# power_supplies.net
KiCad netlist of a schematic drawn in Altium Designer
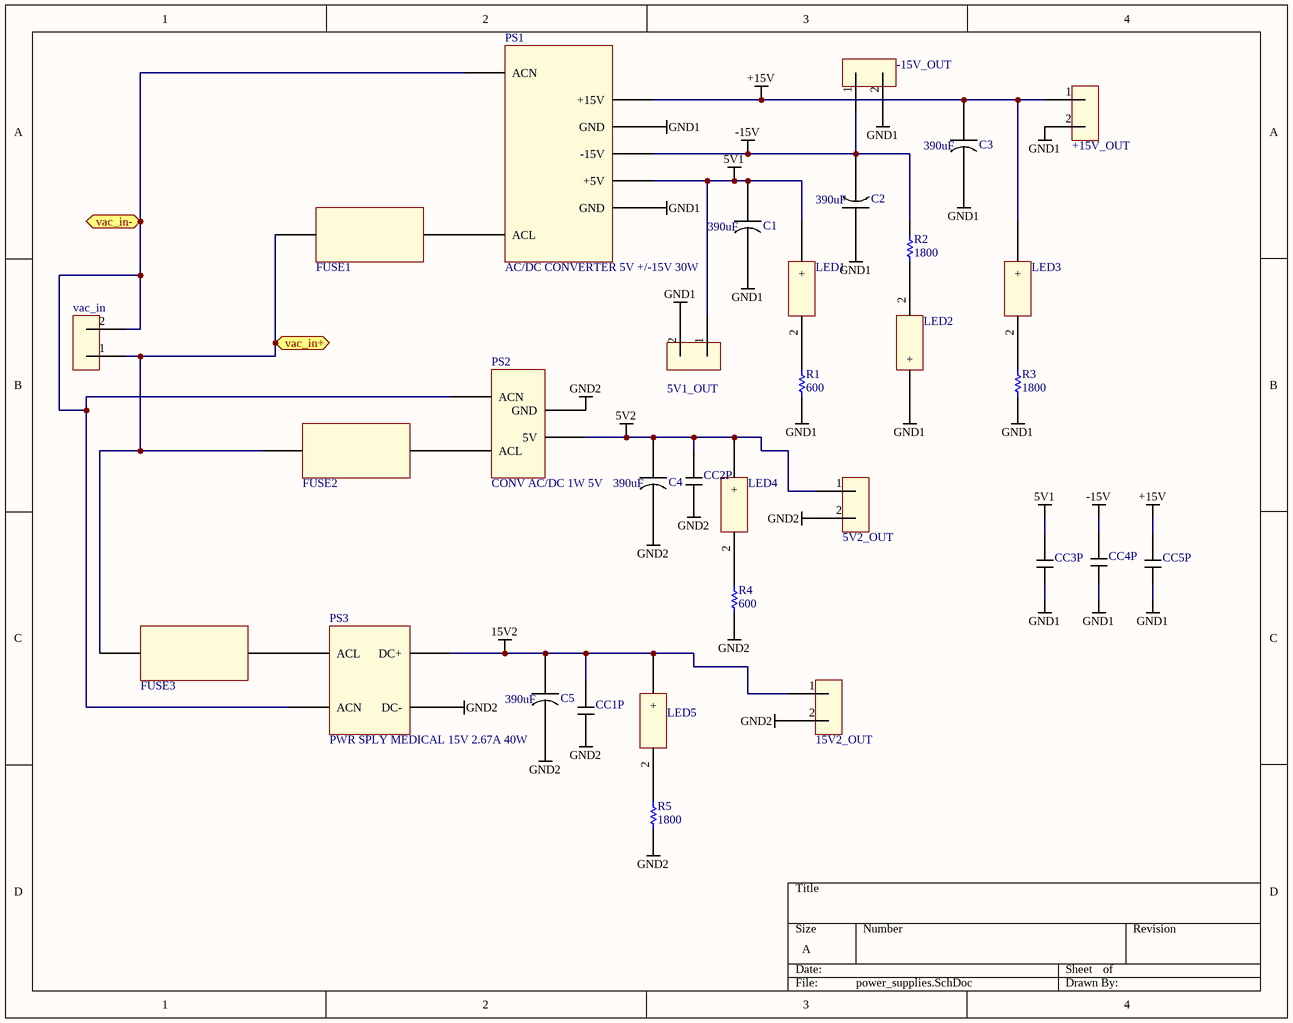
[diagram p0: power_supplies.SchDoc]

(export (version "E")
  (design (tool "Eeschema 10.0.6"))
  (components
    (comp (ref "+15V_OUT")
      (value "5MM_HOR_ENTRY")
      (footprint "5MM_HOR_ENTRY")
      (libsource (lib "") (part "5MM_HOR_ENTRY_1"))
    )
    (comp (ref "-15V_OUT")
      (value "5MM_HOR_ENTRY")
      (footprint "5MM_HOR_ENTRY")
      (libsource (lib "") (part "5MM_HOR_ENTRY_3"))
    )
    (comp (ref "5V1_OUT")
      (value "5MM_HOR_ENTRY")
      (footprint "5MM_HOR_ENTRY")
      (libsource (lib "smartChargerLibrary") (part "5MM_HOR_ENTRY"))
    )
    (comp (ref "5V2_OUT")
      (value "5MM_HOR_ENTRY")
      (footprint "5MM_HOR_ENTRY")
      (libsource (lib "") (part "5MM_HOR_ENTRY_1"))
    )
    (comp (ref "15V2_OUT")
      (value "5MM_HOR_ENTRY")
      (footprint "5MM_HOR_ENTRY")
      (libsource (lib "") (part "5MM_HOR_ENTRY_1"))
    )
    (comp (ref "C1")
      (value "C1")
      (footprint "Cap_Pol_5mm")
      (fields (field (name "CAPACITANCE") "390uF"))
      (libsource (lib "smartChargerLibrary") (part "Cap_Pol_5"))
    )
    (comp (ref "C2")
      (value "C1")
      (footprint "Cap_Pol_5mm")
      (fields (field (name "CAPACITANCE") "390uF"))
      (libsource (lib "smartChargerLibrary") (part "Cap_Pol_5"))
    )
    (comp (ref "C3")
      (value "C1")
      (footprint "Cap_Pol_5mm")
      (fields (field (name "CAPACITANCE") "390uF"))
      (libsource (lib "smartChargerLibrary") (part "Cap_Pol_5"))
    )
    (comp (ref "C4")
      (value "C1")
      (footprint "Cap_Pol_5mm")
      (fields (field (name "CAPACITANCE") "390uF"))
      (libsource (lib "smartChargerLibrary") (part "Cap_Pol_5"))
    )
    (comp (ref "C5")
      (value "C1")
      (footprint "Cap_Pol_5mm")
      (fields (field (name "CAPACITANCE") "390uF"))
      (libsource (lib "smartChargerLibrary") (part "Cap_Pol_5"))
    )
    (comp (ref "CC1P")
      (value "CAP_CERAM_5MM")
      (footprint "CAP_CERAM_5MM")
      (libsource (lib "smartChargerLibrary") (part "CAP_CERAM_5MM"))
    )
    (comp (ref "CC2P")
      (value "CAP_CERAM_5MM")
      (footprint "CAP_CERAM_5MM")
      (libsource (lib "smartChargerLibrary") (part "CAP_CERAM_5MM"))
    )
    (comp (ref "CC3P")
      (value "CAP_CERAM_5MM")
      (footprint "CAP_CERAM_5MM")
      (libsource (lib "smartChargerLibrary") (part "CAP_CERAM_5MM"))
    )
    (comp (ref "CC4P")
      (value "CAP_CERAM_5MM")
      (footprint "CAP_CERAM_5MM")
      (libsource (lib "smartChargerLibrary") (part "CAP_CERAM_5MM"))
    )
    (comp (ref "CC5P")
      (value "CAP_CERAM_5MM")
      (footprint "CAP_CERAM_5MM")
      (libsource (lib "smartChargerLibrary") (part "CAP_CERAM_5MM"))
    )
    (comp (ref "FUSE1")
      (value "fuse < 5A")
      (footprint "Fuse < 5A")
      (libsource (lib "smartChargerLibrary") (part "fuse {lt} 5A"))
    )
    (comp (ref "FUSE2")
      (value "fuse < 5A")
      (footprint "Fuse < 5A")
      (libsource (lib "smartChargerLibrary") (part "fuse {lt} 5A"))
    )
    (comp (ref "FUSE3")
      (value "fuse < 5A")
      (footprint "Fuse < 5A")
      (libsource (lib "smartChargerLibrary") (part "fuse {lt} 5A"))
    )
    (comp (ref "LED1") (value "LED") (footprint "LED") (libsource (lib "smartChargerLibrary") (part "LED")))
    (comp (ref "LED2") (value "LED") (footprint "LED") (libsource (lib "") (part "LED_1")))
    (comp (ref "LED3") (value "LED") (footprint "LED") (libsource (lib "smartChargerLibrary") (part "LED")))
    (comp (ref "LED4") (value "LED") (footprint "LED") (libsource (lib "smartChargerLibrary") (part "LED")))
    (comp (ref "LED5") (value "LED") (footprint "LED") (libsource (lib "smartChargerLibrary") (part "LED")))
    (comp (ref "PS1")
      (value "AC/DC CONVERTER 5V +/-15V 30W")
      (footprint "AC/DC CONVERTER 5V +/-15V 30W")
      (libsource (lib "smartChargerLibrary") (part "AC/DC CONVERTER 5V +/-15V 30W"))
    )
    (comp (ref "PS2")
      (value "CONV AC/DC 1W 5V")
      (footprint "CONV AC/DC 1W 5V")
      (libsource (lib "smartChargerLibrary") (part "CONV AC/DC 1W 5V"))
    )
    (comp (ref "PS3")
      (value "PWR SPLY MEDICAL 15V 2.67A 40W")
      (footprint "PWR SPLY MEDICAL 15V 2.67A 40W")
      (libsource (lib "smartChargerLibrary") (part "PWR SPLY MEDICAL 15V 2.67A 40W"))
    )
    (comp (ref "R1")
      (value "600")
      (footprint "AXIAL-0.3")
      (description "Resistor")
      (fields (field (name "Comment") "Res1") (field (name "PUBLISHER") "Altium Limited"))
      (libsource (lib "Miscellaneous Devices") (part "Res1"))
    )
    (comp (ref "R2")
      (value "1800")
      (footprint "AXIAL-0.3")
      (description "Resistor")
      (fields (field (name "Comment") "Res1") (field (name "PUBLISHER") "Altium Limited"))
      (libsource (lib "Miscellaneous Devices") (part "Res1"))
    )
    (comp (ref "R3")
      (value "1800")
      (footprint "AXIAL-0.3")
      (description "Resistor")
      (fields (field (name "Comment") "Res1") (field (name "PUBLISHER") "Altium Limited"))
      (libsource (lib "Miscellaneous Devices") (part "Res1"))
    )
    (comp (ref "R4")
      (value "600")
      (footprint "AXIAL-0.3")
      (description "Resistor")
      (fields (field (name "Comment") "Res1") (field (name "PUBLISHER") "Altium Limited"))
      (libsource (lib "Miscellaneous Devices") (part "Res1"))
    )
    (comp (ref "R5")
      (value "1800")
      (footprint "AXIAL-0.3")
      (description "Resistor")
      (fields (field (name "Comment") "Res1") (field (name "PUBLISHER") "Altium Limited"))
      (libsource (lib "Miscellaneous Devices") (part "Res1"))
    )
    (comp (ref "vac_in")
      (value "5MM_HOR_ENTRY")
      (footprint "5MM_HOR_ENTRY")
      (libsource (lib "") (part "5MM_HOR_ENTRY_2"))
    )
  )
  (nets
    (net (code "1") (name "+15V") (class "Default")
      (node (ref "+15V_OUT") (pin "1") (pinfunction "1_1") (pintype "passive"))
      (node (ref "C3") (pin "1") (pinfunction "1_1") (pintype "passive"))
      (node (ref "CC5P") (pin "1") (pinfunction "1_1") (pintype "passive"))
      (node (ref "LED3") (pin "1") (pinfunction "+_1") (pintype "passive"))
      (node (ref "PS1") (pin "5") (pinfunction "+15V_5") (pintype "passive"))
    )
    (net (code "2") (name "-15V") (class "Default")
      (node (ref "-15V_OUT") (pin "1") (pinfunction "1_1") (pintype "passive"))
      (node (ref "C2") (pin "2") (pinfunction "2_2") (pintype "passive"))
      (node (ref "CC4P") (pin "1") (pinfunction "1_1") (pintype "passive"))
      (node (ref "PS1") (pin "3") (pinfunction "-15V_3") (pintype "passive"))
      (node (ref "R2") (pin "1") (pinfunction "1_1") (pintype "passive"))
    )
    (net (code "3") (name "/vac_in+") (class "Default")
      (node (ref "FUSE1") (pin "1") (pinfunction "1_1") (pintype "passive"))
      (node (ref "FUSE2") (pin "1") (pinfunction "1_1") (pintype "passive"))
      (node (ref "FUSE3") (pin "1") (pinfunction "1_1") (pintype "passive"))
      (node (ref "vac_in") (pin "1") (pinfunction "1_1") (pintype "passive"))
    )
    (net (code "4") (name "/vac_in-") (class "Default")
      (node (ref "PS1") (pin "ACN") (pinfunction "ACN_ACN") (pintype "passive"))
      (node (ref "PS2") (pin "1") (pinfunction "ACN_1") (pintype "passive"))
      (node (ref "PS3") (pin "2") (pinfunction "ACN_2") (pintype "passive"))
      (node (ref "vac_in") (pin "2") (pinfunction "2_2") (pintype "passive"))
    )
    (net (code "5") (name "5V1") (class "Default")
      (node (ref "5V1_OUT") (pin "1") (pinfunction "1_1") (pintype "passive"))
      (node (ref "C1") (pin "1") (pinfunction "1_1") (pintype "passive"))
      (node (ref "CC3P") (pin "1") (pinfunction "1_1") (pintype "passive"))
      (node (ref "LED1") (pin "1") (pinfunction "+_1") (pintype "passive"))
      (node (ref "PS1") (pin "2") (pinfunction "+5V_2") (pintype "passive"))
    )
    (net (code "6") (name "5V2") (class "Default")
      (node (ref "5V2_OUT") (pin "1") (pinfunction "1_1") (pintype "passive"))
      (node (ref "C4") (pin "1") (pinfunction "1_1") (pintype "passive"))
      (node (ref "CC2P") (pin "1") (pinfunction "1_1") (pintype "passive"))
      (node (ref "LED4") (pin "1") (pinfunction "+_1") (pintype "passive"))
      (node (ref "PS2") (pin "4") (pinfunction "5V_4") (pintype "passive"))
    )
    (net (code "7") (name "15V2") (class "Default")
      (node (ref "15V2_OUT") (pin "1") (pinfunction "1_1") (pintype "passive"))
      (node (ref "C5") (pin "1") (pinfunction "1_1") (pintype "passive"))
      (node (ref "CC1P") (pin "1") (pinfunction "1_1") (pintype "passive"))
      (node (ref "LED5") (pin "1") (pinfunction "+_1") (pintype "passive"))
      (node (ref "PS3") (pin "3") (pinfunction "DC+_3") (pintype "passive"))
    )
    (net (code "8") (name "GND1") (class "Default")
      (node (ref "+15V_OUT") (pin "2") (pinfunction "2_2") (pintype "passive"))
      (node (ref "-15V_OUT") (pin "2") (pinfunction "2_2") (pintype "passive"))
      (node (ref "5V1_OUT") (pin "2") (pinfunction "2_2") (pintype "passive"))
      (node (ref "C1") (pin "2") (pinfunction "2_2") (pintype "passive"))
      (node (ref "C2") (pin "1") (pinfunction "1_1") (pintype "passive"))
      (node (ref "C3") (pin "2") (pinfunction "2_2") (pintype "passive"))
      (node (ref "CC3P") (pin "2") (pinfunction "2_2") (pintype "passive"))
      (node (ref "CC4P") (pin "2") (pinfunction "2_2") (pintype "passive"))
      (node (ref "CC5P") (pin "2") (pinfunction "2_2") (pintype "passive"))
      (node (ref "LED2") (pin "1") (pinfunction "+_1") (pintype "passive"))
      (node (ref "PS1") (pin "1") (pinfunction "GND_1") (pintype "passive"))
      (node (ref "PS1") (pin "4") (pinfunction "GND_4") (pintype "passive"))
      (node (ref "R1") (pin "1") (pinfunction "1_1") (pintype "passive"))
      (node (ref "R3") (pin "1") (pinfunction "1_1") (pintype "passive"))
    )
    (net (code "9") (name "GND2") (class "Default")
      (node (ref "15V2_OUT") (pin "2") (pinfunction "2_2") (pintype "passive"))
      (node (ref "5V2_OUT") (pin "2") (pinfunction "2_2") (pintype "passive"))
      (node (ref "C4") (pin "2") (pinfunction "2_2") (pintype "passive"))
      (node (ref "C5") (pin "2") (pinfunction "2_2") (pintype "passive"))
      (node (ref "CC1P") (pin "2") (pinfunction "2_2") (pintype "passive"))
      (node (ref "CC2P") (pin "2") (pinfunction "2_2") (pintype "passive"))
      (node (ref "PS2") (pin "3") (pinfunction "GND_3") (pintype "passive"))
      (node (ref "PS3") (pin "5") (pinfunction "DC-_5") (pintype "passive"))
      (node (ref "R4") (pin "1") (pinfunction "1_1") (pintype "passive"))
      (node (ref "R5") (pin "2") (pinfunction "2_2") (pintype "passive"))
    )
    (net (code "10") (name "Net-(FUSE1-Pad2)") (class "Default")
      (node (ref "FUSE1") (pin "2") (pinfunction "2_2") (pintype "passive"))
      (node (ref "PS1") (pin "ACL") (pinfunction "ACL_ACL") (pintype "passive"))
    )
    (net (code "11") (name "Net-(LED1--)") (class "Default")
      (node (ref "LED1") (pin "2") (pinfunction "-_2") (pintype "passive"))
      (node (ref "R1") (pin "2") (pinfunction "2_2") (pintype "passive"))
    )
    (net (code "12") (name "Net-(LED2--)") (class "Default")
      (node (ref "LED2") (pin "2") (pinfunction "-_2") (pintype "passive"))
      (node (ref "R2") (pin "2") (pinfunction "2_2") (pintype "passive"))
    )
    (net (code "13") (name "Net-(LED3--)") (class "Default")
      (node (ref "LED3") (pin "2") (pinfunction "-_2") (pintype "passive"))
      (node (ref "R3") (pin "2") (pinfunction "2_2") (pintype "passive"))
    )
    (net (code "14") (name "Net-(LED4--)") (class "Default")
      (node (ref "LED4") (pin "2") (pinfunction "-_2") (pintype "passive"))
      (node (ref "R4") (pin "2") (pinfunction "2_2") (pintype "passive"))
    )
    (net (code "15") (name "Net-(LED5--)") (class "Default")
      (node (ref "LED5") (pin "2") (pinfunction "-_2") (pintype "passive"))
      (node (ref "R5") (pin "1") (pinfunction "1_1") (pintype "passive"))
    )
    (net (code "16") (name "Net-(PS2-ACL)") (class "Default")
      (node (ref "FUSE2") (pin "2") (pinfunction "2_2") (pintype "passive"))
      (node (ref "PS2") (pin "2") (pinfunction "ACL_2") (pintype "passive"))
    )
    (net (code "17") (name "Net-(PS3-ACL)") (class "Default")
      (node (ref "FUSE3") (pin "2") (pinfunction "2_2") (pintype "passive"))
      (node (ref "PS3") (pin "1") (pinfunction "ACL_1") (pintype "passive"))
    )
  )
)
